# Battery_board_V4_3.net
KiCad netlist of a schematic drawn in EAGLE
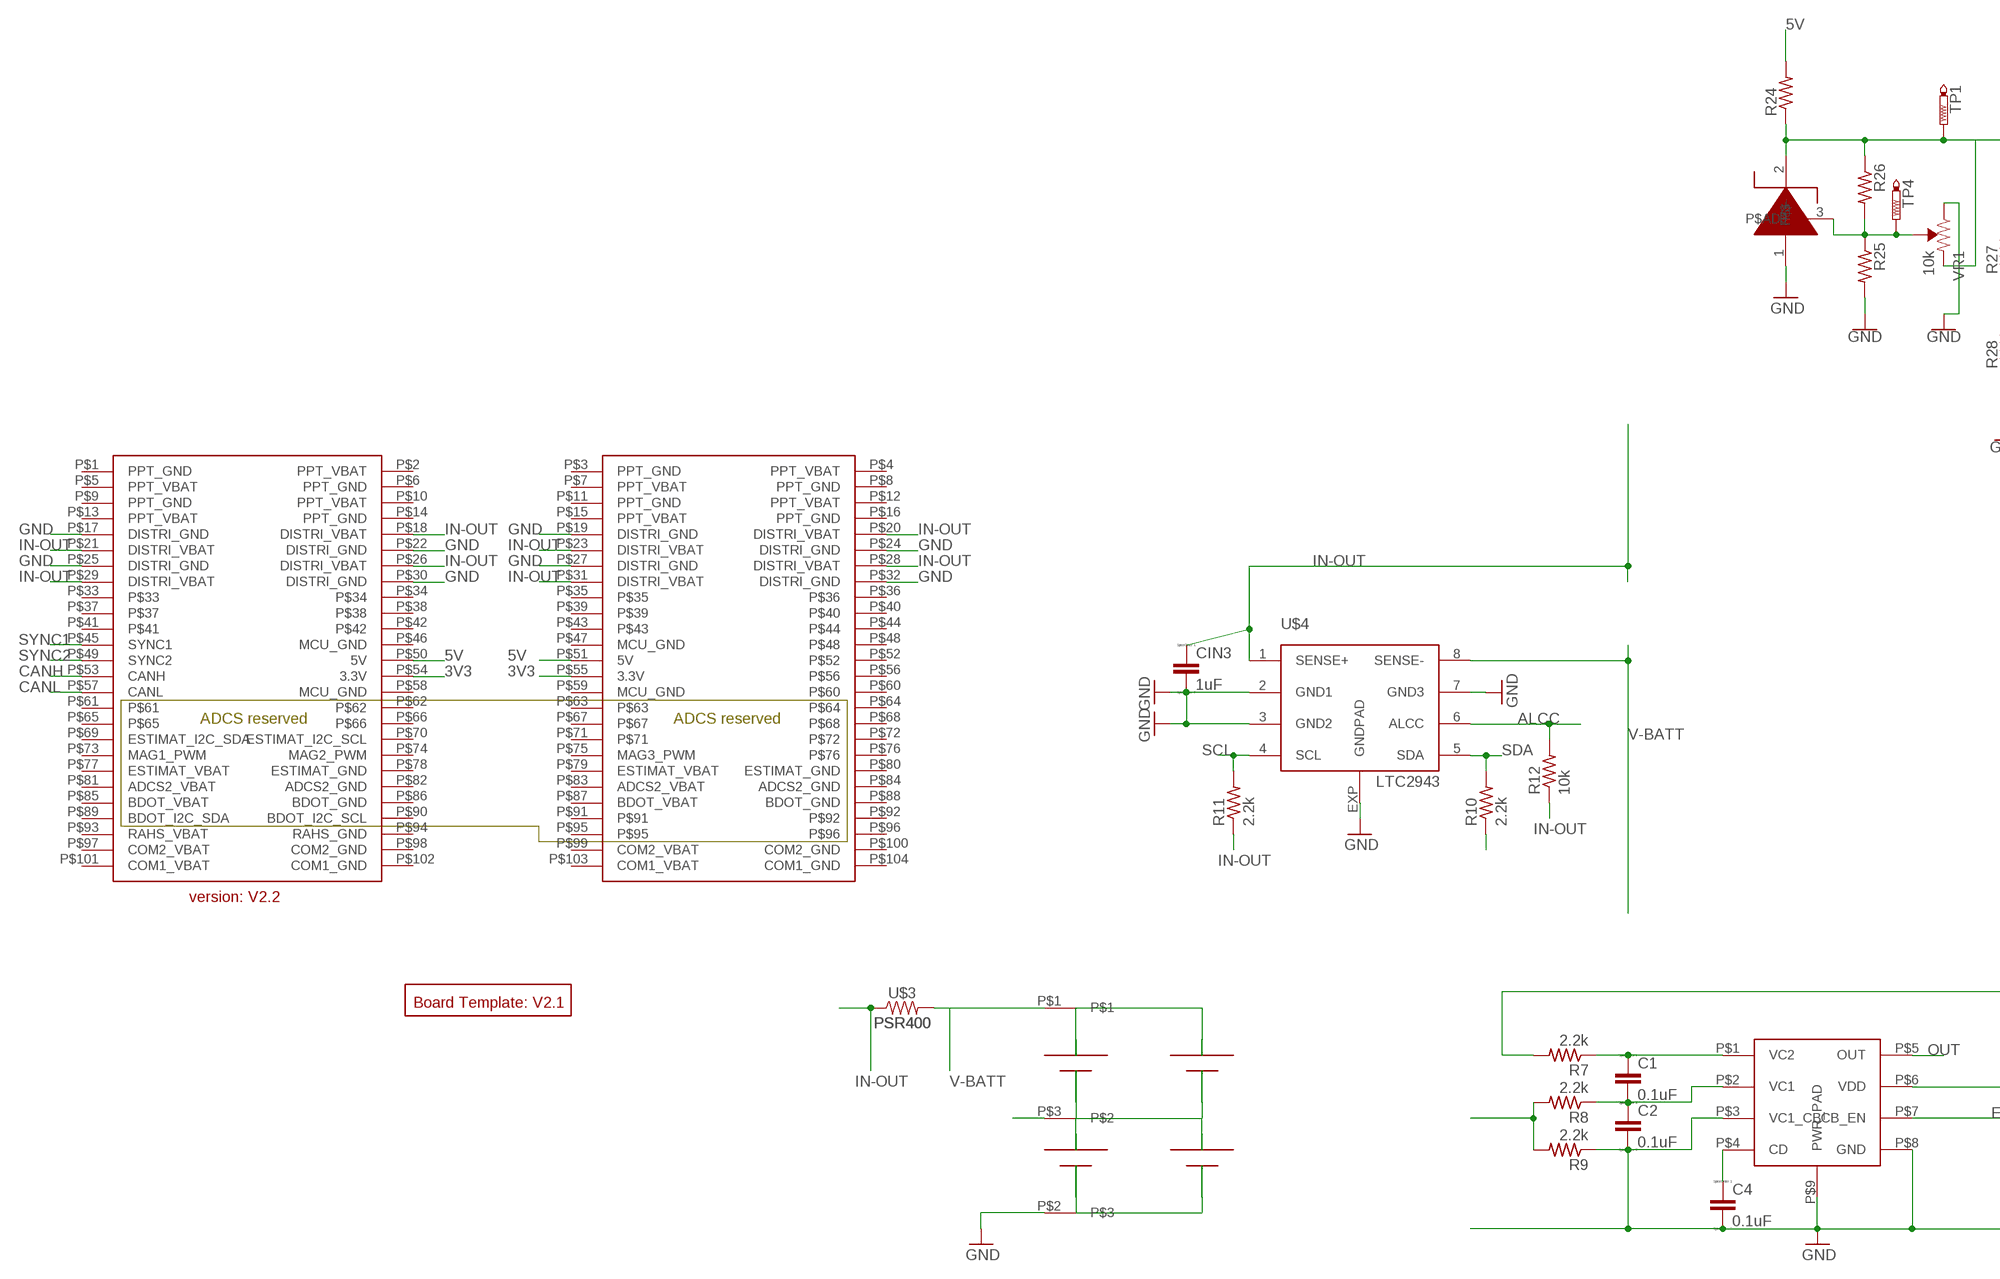
[diagram p0: schematic, sheet 1, part 1 of 2]
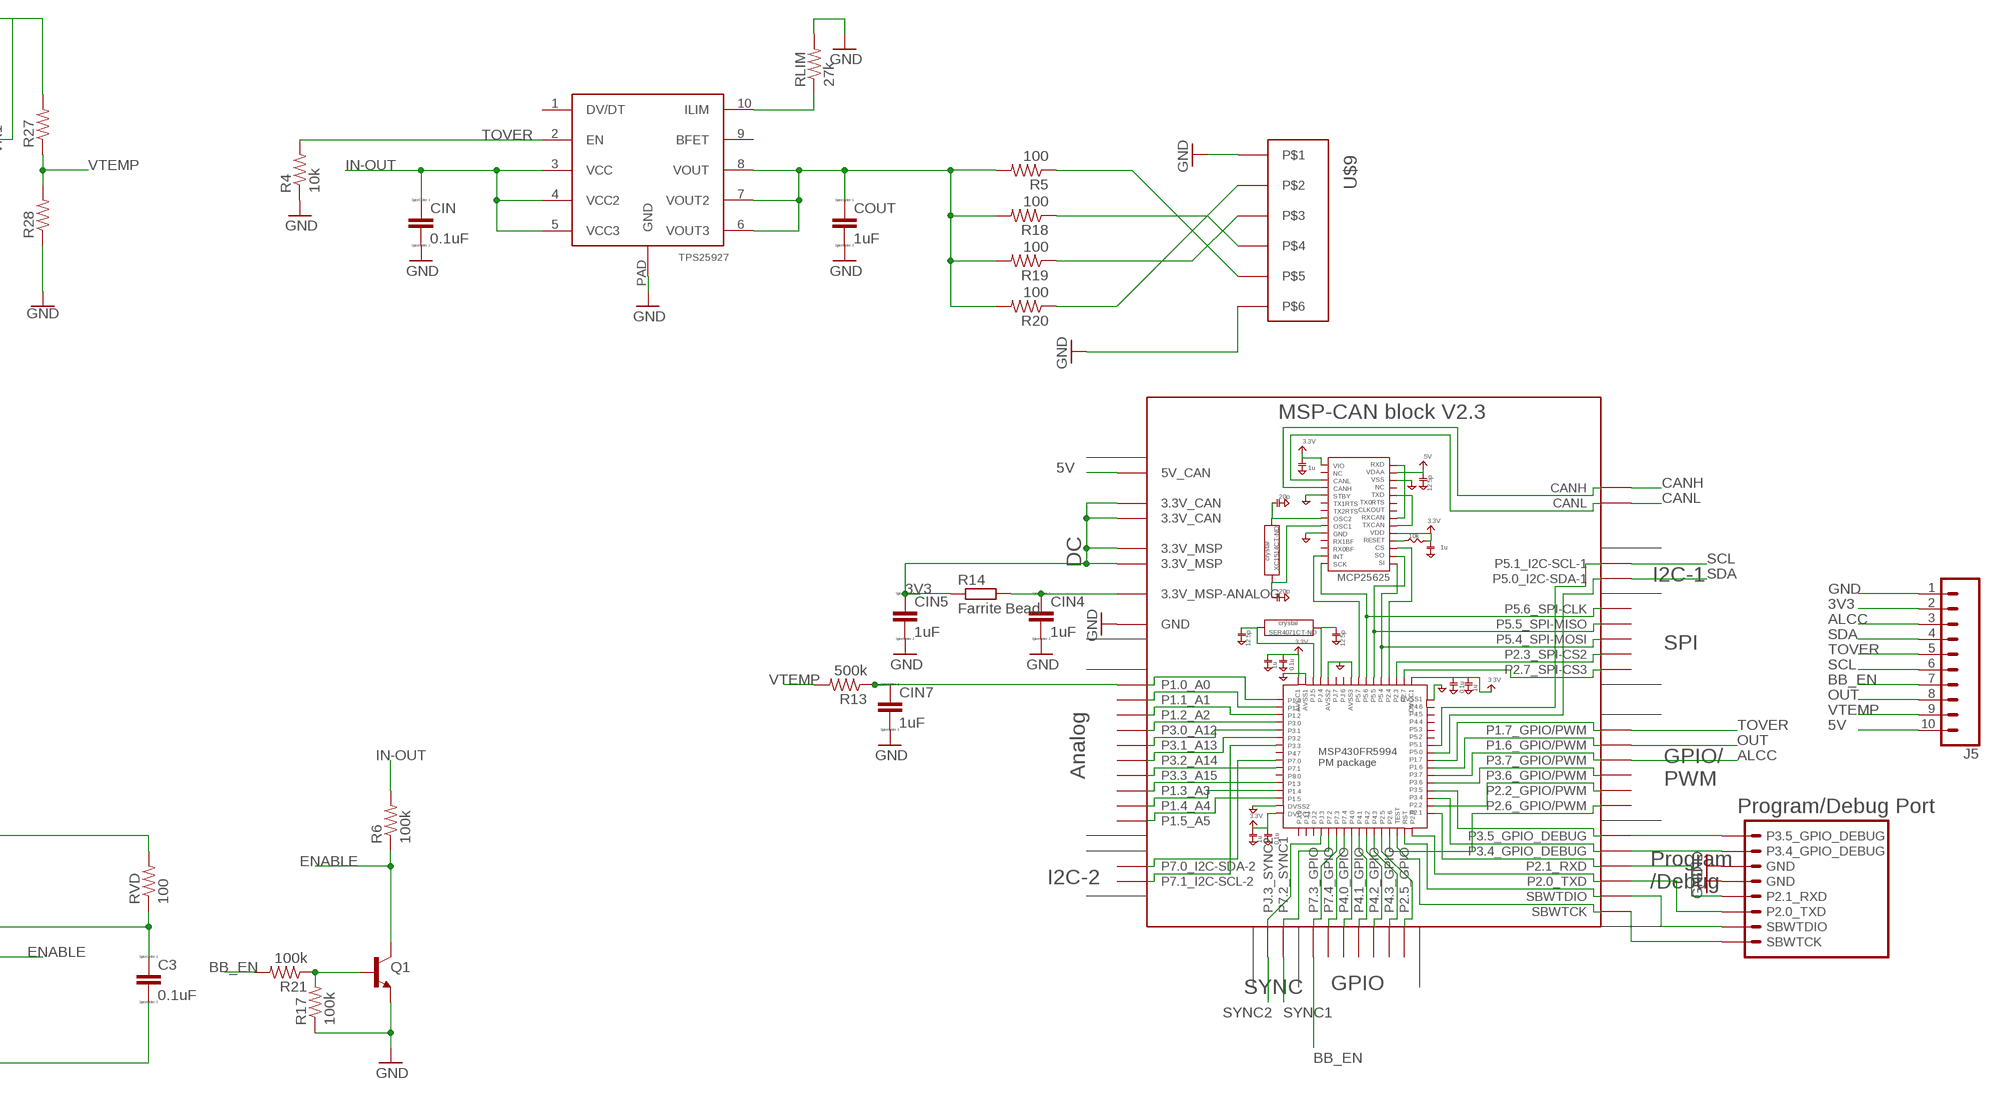
[diagram p1: schematic, sheet 1, part 2 of 2]

(export (version "E")
  (design (tool "Eeschema 10.0.6"))
  (components
    (comp (ref "C1")
      (value "0.1uF")
      (footprint "eagle-import:C0805")
      (libsource (lib "eagle-import") (part "C"))
    )
    (comp (ref "C2")
      (value "0.1uF")
      (footprint "eagle-import:C0805")
      (libsource (lib "eagle-import") (part "C"))
    )
    (comp (ref "C3")
      (value "0.1uF")
      (footprint "eagle-import:C0805")
      (libsource (lib "eagle-import") (part "C"))
    )
    (comp (ref "C4")
      (value "0.1uF")
      (footprint "eagle-import:C0805")
      (libsource (lib "eagle-import") (part "C"))
    )
    (comp (ref "CIN")
      (value "0.1uF")
      (footprint "eagle-import:C0805")
      (libsource (lib "eagle-import") (part "C"))
    )
    (comp (ref "CIN3")
      (value "1uF")
      (footprint "eagle-import:C0805")
      (libsource (lib "eagle-import") (part "C"))
    )
    (comp (ref "CIN4")
      (value "1uF")
      (footprint "eagle-import:C0805")
      (libsource (lib "eagle-import") (part "C"))
    )
    (comp (ref "CIN5")
      (value "1uF")
      (footprint "eagle-import:C0805")
      (libsource (lib "eagle-import") (part "C"))
    )
    (comp (ref "CIN7")
      (value "1uF")
      (footprint "eagle-import:C0805")
      (libsource (lib "eagle-import") (part "C"))
    )
    (comp (ref "COUT")
      (value "1uF")
      (footprint "eagle-import:C0805")
      (libsource (lib "eagle-import") (part "C"))
    )
    (comp (ref "J5")
      (value "CONN_10LOCK")
      (footprint "eagle-import:1X10_LOCK")
      (libsource (lib "eagle-import") (part "CONN_10LOCK"))
    )
    (comp (ref "Q1")
      (value "TRANS_NPN-MMBT2222AL")
      (footprint "eagle-import:SOT23-3")
      (libsource (lib "eagle-import") (part "TRANS_NPN-MMBT2222AL"))
    )
    (comp (ref "R4")
      (value "10k")
      (footprint "eagle-import:R0805")
      (libsource (lib "eagle-import") (part "R-US_R0805"))
    )
    (comp (ref "R5")
      (value "100")
      (footprint "eagle-import:R0805")
      (libsource (lib "eagle-import") (part "R-US_R0805"))
    )
    (comp (ref "R6")
      (value "100k")
      (footprint "eagle-import:R0805")
      (libsource (lib "eagle-import") (part "R-US_R0805"))
    )
    (comp (ref "R7")
      (value "2.2k")
      (footprint "eagle-import:R0805")
      (libsource (lib "eagle-import") (part "R-US_R0805"))
    )
    (comp (ref "R8")
      (value "2.2k")
      (footprint "eagle-import:R0805")
      (libsource (lib "eagle-import") (part "R-US_R0805"))
    )
    (comp (ref "R9")
      (value "2.2k")
      (footprint "eagle-import:R0805")
      (libsource (lib "eagle-import") (part "R-US_R0805"))
    )
    (comp (ref "R10")
      (value "2.2k")
      (footprint "eagle-import:R0805")
      (libsource (lib "eagle-import") (part "R-US_R0805"))
    )
    (comp (ref "R11")
      (value "2.2k")
      (footprint "eagle-import:R0805")
      (libsource (lib "eagle-import") (part "R-US_R0805"))
    )
    (comp (ref "R12")
      (value "10k")
      (footprint "eagle-import:R0805")
      (libsource (lib "eagle-import") (part "R-US_R0805"))
    )
    (comp (ref "R13")
      (value "500k")
      (footprint "eagle-import:R0805")
      (libsource (lib "eagle-import") (part "R-US_R0805"))
    )
    (comp (ref "R14")
      (value "Farrite Bead")
      (footprint "eagle-import:R1206")
      (libsource (lib "eagle-import") (part "R-EU_R1206"))
    )
    (comp (ref "R17")
      (value "100k")
      (footprint "eagle-import:M0805")
      (libsource (lib "eagle-import") (part "R-US_M0805"))
    )
    (comp (ref "R18")
      (value "100")
      (footprint "eagle-import:R0805")
      (libsource (lib "eagle-import") (part "R-US_R0805"))
    )
    (comp (ref "R19")
      (value "100")
      (footprint "eagle-import:R0805")
      (libsource (lib "eagle-import") (part "R-US_R0805"))
    )
    (comp (ref "R20")
      (value "100")
      (footprint "eagle-import:R0805")
      (libsource (lib "eagle-import") (part "R-US_R0805"))
    )
    (comp (ref "R21")
      (value "100k")
      (footprint "eagle-import:M0805")
      (libsource (lib "eagle-import") (part "R-US_M0805"))
    )
    (comp (ref "R24")
      (value "R-US_R0805")
      (footprint "eagle-import:R0805")
      (libsource (lib "eagle-import") (part "R-US_R0805"))
    )
    (comp (ref "R25")
      (value "R-US_R0805")
      (footprint "eagle-import:R0805")
      (libsource (lib "eagle-import") (part "R-US_R0805"))
    )
    (comp (ref "R26")
      (value "R-US_R0805")
      (footprint "eagle-import:R0805")
      (libsource (lib "eagle-import") (part "R-US_R0805"))
    )
    (comp (ref "R27")
      (value "R-US_R0805")
      (footprint "eagle-import:R0805")
      (libsource (lib "eagle-import") (part "R-US_R0805"))
    )
    (comp (ref "R28")
      (value "R-US_R0805")
      (footprint "eagle-import:R0805")
      (libsource (lib "eagle-import") (part "R-US_R0805"))
    )
    (comp (ref "RLIM")
      (value "27k")
      (footprint "eagle-import:R0805")
      (libsource (lib "eagle-import") (part "R-US_R0805"))
    )
    (comp (ref "RVD")
      (value "100")
      (footprint "eagle-import:R0805")
      (libsource (lib "eagle-import") (part "R-US_R0805"))
    )
    (comp (ref "TP1")
      (value "PTR1PAD1-13Y")
      (footprint "eagle-import:P1-13Y")
      (libsource (lib "eagle-import") (part "PTR1PAD1-13Y"))
    )
    (comp (ref "TP4")
      (value "PTR1PAD1-13Y")
      (footprint "eagle-import:P1-13Y")
      (libsource (lib "eagle-import") (part "PTR1PAD1-13Y"))
    )
    (comp (ref "U$1")
      (value "MSP-CAN_BLOCK")
      (footprint "eagle-import:MSP-CAN_BLOCK")
      (libsource (lib "eagle-import") (part "MSP-CAN_BLOCK"))
    )
    (comp (ref "U$2")
      (value "PROGRAM/DEBUG_PORT")
      (footprint "eagle-import:1X08_CONNECTOR")
      (libsource (lib "eagle-import") (part "PROGRAM/DEBUG_PORT"))
    )
    (comp (ref "U$3")
      (value "PSR400")
      (footprint "eagle-import:PSR400")
      (libsource (lib "eagle-import") (part "PSR400"))
    )
    (comp (ref "U$4")
      (value "LTC2943")
      (footprint "eagle-import:DFN8(3X3)LT")
      (libsource (lib "eagle-import") (part "LTC2943"))
    )
    (comp (ref "U$5")
      (value "TPS252927")
      (footprint "eagle-import:VSON10")
      (libsource (lib "eagle-import") (part "TPS252927"))
    )
    (comp (ref "U$6")
      (value "POWER_PACK")
      (footprint "eagle-import:BATTERY_PACK")
      (libsource (lib "eagle-import") (part "POWER_PACK"))
    )
    (comp (ref "U$7")
      (value "PC104_CONNECTOR")
      (footprint "eagle-import:PC104_CONNECTOR")
      (libsource (lib "eagle-import") (part "PC104_CONNECTOR"))
    )
    (comp (ref "U$8")
      (value "BQ29209")
      (footprint "eagle-import:VSON8")
      (libsource (lib "eagle-import") (part "BQ29209"))
    )
    (comp (ref "U$9")
      (value "PICOLOCK_6")
      (footprint "eagle-import:PICOLOCK_6")
      (libsource (lib "eagle-import") (part "PICOLOCK_6"))
    )
    (comp (ref "U$10")
      (value "LM135Z")
      (footprint "eagle-import:TO-92-3")
      (libsource (lib "eagle-import") (part "LM135Z"))
    )
    (comp (ref "U$11")
      (value "BOARD_TEMPLATE")
      (footprint "eagle-import:BOARD_TEMPLATE")
      (libsource (lib "eagle-import") (part "BOARD_TEMPLATE"))
    )
    (comp (ref "VR1")
      (value "10k")
      (footprint "eagle-import:TRIMPOT-SMD-TC33X")
      (libsource (lib "eagle-import") (part "TRIMPOT-SMD-3MM-OPEN-1/10W-25%"))
    )
  )
  (nets
    (net (code "1") (name "/3V3") (class "Default")
      (node (ref "CIN5") (pin "1") (pinfunction "1_1") (pintype "passive"))
      (node (ref "J5") (pin "2") (pinfunction "2_2") (pintype "passive"))
      (node (ref "R14") (pin "1") (pinfunction "1_1") (pintype "passive"))
      (node (ref "U$1") (pin "3.3V@CAN1") (pinfunction "3.3V_CAN_3.3V@CAN1") (pintype "bidirectional"))
      (node (ref "U$1") (pin "3.3V@CAN2") (pinfunction "3.3V_CAN_3.3V@CAN2") (pintype "bidirectional"))
      (node (ref "U$1") (pin "3.3V@MSP1") (pinfunction "3.3V_MSP_3.3V@MSP1") (pintype "bidirectional"))
      (node (ref "U$1") (pin "3.3V@MSP2") (pinfunction "3.3V_MSP_3.3V@MSP2") (pintype "bidirectional"))
      (node (ref "U$7") (pin "P$54") (pinfunction "3.3V_P$54") (pintype "bidirectional"))
      (node (ref "U$7") (pin "P$55") (pinfunction "3.3V_P$55") (pintype "bidirectional"))
    )
    (net (code "2") (name "/5V") (class "Default")
      (node (ref "J5") (pin "10") (pinfunction "10_10") (pintype "passive"))
      (node (ref "R24") (pin "2") (pinfunction "2_2") (pintype "passive"))
      (node (ref "U$1") (pin "5V") (pinfunction "5V_CAN_5V") (pintype "bidirectional"))
      (node (ref "U$7") (pin "P$50") (pinfunction "5V_P$50") (pintype "bidirectional"))
      (node (ref "U$7") (pin "P$51") (pinfunction "5V_P$51") (pintype "bidirectional"))
    )
    (net (code "3") (name "/ALCC") (class "Default")
      (node (ref "J5") (pin "3") (pinfunction "3_3") (pintype "passive"))
      (node (ref "R12") (pin "2") (pinfunction "2_2") (pintype "passive"))
      (node (ref "U$1") (pin "P3.7_GPIO/PWM") (pinfunction "P3.7_GPIO/PWM_P3.7_GPIO/PWM") (pintype "bidirectional"))
      (node (ref "U$4") (pin "6") (pinfunction "ALCC_6") (pintype "bidirectional"))
    )
    (net (code "4") (name "/BB_EN") (class "Default")
      (node (ref "J5") (pin "7") (pinfunction "7_7") (pintype "passive"))
      (node (ref "R21") (pin "2") (pinfunction "2_2") (pintype "passive"))
      (node (ref "U$1") (pin "P7.3_GPIO") (pinfunction "P7.3_GPIO_P7.3_GPIO") (pintype "bidirectional"))
    )
    (net (code "5") (name "/BT-NODE") (class "Default")
      (node (ref "R8") (pin "2") (pinfunction "2_2") (pintype "passive"))
      (node (ref "R9") (pin "2") (pinfunction "2_2") (pintype "passive"))
      (node (ref "U$6") (pin "P$3") (pinfunction "P$2_P$3") (pintype "bidirectional"))
    )
    (net (code "6") (name "/CANH") (class "Default")
      (node (ref "U$1") (pin "CANH") (pinfunction "CANH_CANH") (pintype "bidirectional"))
      (node (ref "U$7") (pin "P$53") (pinfunction "CANH_P$53") (pintype "bidirectional"))
    )
    (net (code "7") (name "/CANL") (class "Default")
      (node (ref "U$1") (pin "CANL") (pinfunction "CANL_CANL") (pintype "bidirectional"))
      (node (ref "U$7") (pin "P$57") (pinfunction "CANL_P$57") (pintype "bidirectional"))
    )
    (net (code "8") (name "/ENABLE") (class "Default")
      (node (ref "Q1") (pin "3") (pinfunction "C_3") (pintype "passive"))
      (node (ref "R6") (pin "1") (pinfunction "1_1") (pintype "passive"))
      (node (ref "U$8") (pin "P$7") (pinfunction "CB_EN_P$7") (pintype "bidirectional"))
    )
    (net (code "9") (name "/IN-OUT") (class "Default")
      (node (ref "CIN") (pin "1") (pinfunction "1_1") (pintype "passive"))
      (node (ref "CIN3") (pin "1") (pinfunction "1_1") (pintype "passive"))
      (node (ref "R10") (pin "1") (pinfunction "1_1") (pintype "passive"))
      (node (ref "R11") (pin "1") (pinfunction "1_1") (pintype "passive"))
      (node (ref "R12") (pin "1") (pinfunction "1_1") (pintype "passive"))
      (node (ref "R6") (pin "2") (pinfunction "2_2") (pintype "passive"))
      (node (ref "R7") (pin "2") (pinfunction "2_2") (pintype "passive"))
      (node (ref "RVD") (pin "2") (pinfunction "2_2") (pintype "passive"))
      (node (ref "U$3") (pin "P$1") (pinfunction "1_P$1") (pintype "passive"))
      (node (ref "U$4") (pin "1") (pinfunction "SENSE+_1") (pintype "bidirectional"))
      (node (ref "U$5") (pin "3") (pinfunction "VCC_3") (pintype "bidirectional"))
      (node (ref "U$5") (pin "4") (pinfunction "VCC2_4") (pintype "bidirectional"))
      (node (ref "U$5") (pin "5") (pinfunction "VCC3_5") (pintype "bidirectional"))
      (node (ref "U$7") (pin "P$18") (pinfunction "DISTRI_VBAT_P$18") (pintype "bidirectional"))
      (node (ref "U$7") (pin "P$20") (pinfunction "DISTRI_VBAT_P$20") (pintype "bidirectional"))
      (node (ref "U$7") (pin "P$21") (pinfunction "DISTRI_VBAT_P$21") (pintype "bidirectional"))
      (node (ref "U$7") (pin "P$23") (pinfunction "DISTRI_VBAT_P$23") (pintype "bidirectional"))
      (node (ref "U$7") (pin "P$26") (pinfunction "DISTRI_VBAT_P$26") (pintype "bidirectional"))
      (node (ref "U$7") (pin "P$28") (pinfunction "DISTRI_VBAT_P$28") (pintype "bidirectional"))
      (node (ref "U$7") (pin "P$29") (pinfunction "DISTRI_VBAT_P$29") (pintype "bidirectional"))
      (node (ref "U$7") (pin "P$31") (pinfunction "DISTRI_VBAT_P$31") (pintype "bidirectional"))
    )
    (net (code "10") (name "/OUT") (class "Default")
      (node (ref "J5") (pin "8") (pinfunction "8_8") (pintype "passive"))
      (node (ref "U$1") (pin "P1.6_GPIO/PWM") (pinfunction "P1.6_GPIO/PWM_P1.6_GPIO/PWM") (pintype "bidirectional"))
      (node (ref "U$8") (pin "P$5") (pinfunction "OUT_P$5") (pintype "bidirectional"))
    )
    (net (code "11") (name "/SCL") (class "Default")
      (node (ref "J5") (pin "6") (pinfunction "6_6") (pintype "passive"))
      (node (ref "R11") (pin "2") (pinfunction "2_2") (pintype "passive"))
      (node (ref "U$1") (pin "P5.1_I2C-SCL-1") (pinfunction "P5.1_I2C-SCL-1_P5.1_I2C-SCL-1") (pintype "bidirectional"))
      (node (ref "U$4") (pin "4") (pinfunction "SCL_4") (pintype "bidirectional"))
    )
    (net (code "12") (name "/SDA") (class "Default")
      (node (ref "J5") (pin "4") (pinfunction "4_4") (pintype "passive"))
      (node (ref "R10") (pin "2") (pinfunction "2_2") (pintype "passive"))
      (node (ref "U$1") (pin "P5.0_I2C-SDA-1") (pinfunction "P5.0_I2C-SDA-1_P5.0_I2C-SDA-1") (pintype "bidirectional"))
      (node (ref "U$4") (pin "5") (pinfunction "SDA_5") (pintype "bidirectional"))
    )
    (net (code "13") (name "/SYNC1") (class "Default")
      (node (ref "U$1") (pin "P7.2_SYNC1") (pinfunction "P7.2_SYNC1_P7.2_SYNC1") (pintype "bidirectional"))
      (node (ref "U$7") (pin "P$45") (pinfunction "SYNC1_P$45") (pintype "bidirectional"))
    )
    (net (code "14") (name "/SYNC2") (class "Default")
      (node (ref "U$1") (pin "PJ.3_SYNC2") (pinfunction "PJ.3_SYNC2_PJ.3_SYNC2") (pintype "bidirectional"))
      (node (ref "U$7") (pin "P$49") (pinfunction "SYNC2_P$49") (pintype "bidirectional"))
    )
    (net (code "15") (name "/TOVER") (class "Default")
      (node (ref "J5") (pin "5") (pinfunction "5_5") (pintype "passive"))
      (node (ref "R4") (pin "2") (pinfunction "2_2") (pintype "passive"))
      (node (ref "U$1") (pin "P1.7_GPIO/PWM") (pinfunction "P1.7_GPIO/PWM_P1.7_GPIO/PWM") (pintype "bidirectional"))
      (node (ref "U$5") (pin "2") (pinfunction "EN_2") (pintype "bidirectional"))
    )
    (net (code "16") (name "/V-BATT") (class "Default")
      (node (ref "U$3") (pin "P$2") (pinfunction "2_P$2") (pintype "passive"))
      (node (ref "U$4") (pin "8") (pinfunction "SENSE-_8") (pintype "bidirectional"))
      (node (ref "U$6") (pin "P$1") (pinfunction "P$1_P$1") (pintype "bidirectional"))
    )
    (net (code "17") (name "/VTEMP") (class "Default")
      (node (ref "J5") (pin "9") (pinfunction "9_9") (pintype "passive"))
      (node (ref "R13") (pin "2") (pinfunction "2_2") (pintype "passive"))
      (node (ref "R27") (pin "1") (pinfunction "1_1") (pintype "passive"))
      (node (ref "R28") (pin "2") (pinfunction "2_2") (pintype "passive"))
    )
    (net (code "18") (name "GND") (class "Default")
      (node (ref "C2") (pin "2") (pinfunction "2_2") (pintype "passive"))
      (node (ref "C3") (pin "2") (pinfunction "2_2") (pintype "passive"))
      (node (ref "C4") (pin "2") (pinfunction "2_2") (pintype "passive"))
      (node (ref "CIN") (pin "2") (pinfunction "2_2") (pintype "passive"))
      (node (ref "CIN3") (pin "2") (pinfunction "2_2") (pintype "passive"))
      (node (ref "CIN4") (pin "2") (pinfunction "2_2") (pintype "passive"))
      (node (ref "CIN5") (pin "2") (pinfunction "2_2") (pintype "passive"))
      (node (ref "CIN7") (pin "2") (pinfunction "2_2") (pintype "passive"))
      (node (ref "COUT") (pin "2") (pinfunction "2_2") (pintype "passive"))
      (node (ref "J5") (pin "1") (pinfunction "1_1") (pintype "passive"))
      (node (ref "Q1") (pin "2") (pinfunction "E_2") (pintype "passive"))
      (node (ref "R17") (pin "1") (pinfunction "1_1") (pintype "passive"))
      (node (ref "R25") (pin "2") (pinfunction "2_2") (pintype "passive"))
      (node (ref "R28") (pin "1") (pinfunction "1_1") (pintype "passive"))
      (node (ref "R4") (pin "1") (pinfunction "1_1") (pintype "passive"))
      (node (ref "R9") (pin "1") (pinfunction "1_1") (pintype "passive"))
      (node (ref "RLIM") (pin "2") (pinfunction "2_2") (pintype "passive"))
      (node (ref "U$1") (pin "GND@1") (pinfunction "GND_GND@1") (pintype "bidirectional"))
      (node (ref "U$1") (pin "GND@10") (pinfunction "GND_GND@10") (pintype "bidirectional"))
      (node (ref "U$1") (pin "GND@11") (pinfunction "GND_GND@11") (pintype "bidirectional"))
      (node (ref "U$1") (pin "GND@12") (pinfunction "GND_GND@12") (pintype "bidirectional"))
      (node (ref "U$1") (pin "GND@13") (pinfunction "GND_GND@13") (pintype "bidirectional"))
      (node (ref "U$1") (pin "GND@14") (pinfunction "GND_GND@14") (pintype "bidirectional"))
      (node (ref "U$1") (pin "GND@15") (pinfunction "GND_GND@15") (pintype "bidirectional"))
      (node (ref "U$1") (pin "GND@16") (pinfunction "GND_GND@16") (pintype "bidirectional"))
      (node (ref "U$1") (pin "GND@17") (pinfunction "GND_GND@17") (pintype "bidirectional"))
      (node (ref "U$1") (pin "GND@2") (pinfunction "GND_GND@2") (pintype "bidirectional"))
      (node (ref "U$1") (pin "GND@26") (pinfunction "GND_GND@26") (pintype "bidirectional"))
      (node (ref "U$1") (pin "GND@3") (pinfunction "GND_GND@3") (pintype "bidirectional"))
      (node (ref "U$1") (pin "GND@4") (pinfunction "GND_GND@4") (pintype "bidirectional"))
      (node (ref "U$1") (pin "GND@5") (pinfunction "GND_GND@5") (pintype "bidirectional"))
      (node (ref "U$1") (pin "GND@7") (pinfunction "GND_GND@7") (pintype "bidirectional"))
      (node (ref "U$1") (pin "GND@8") (pinfunction "GND_GND@8") (pintype "bidirectional"))
      (node (ref "U$1") (pin "GND@9") (pinfunction "GND_GND@9") (pintype "bidirectional"))
      (node (ref "U$10") (pin "1") (pinfunction "P$-_1") (pintype "bidirectional"))
      (node (ref "U$2") (pin "5") (pinfunction "GND_5") (pintype "bidirectional"))
      (node (ref "U$2") (pin "6") (pinfunction "GND_6") (pintype "bidirectional"))
      (node (ref "U$4") (pin "2") (pinfunction "GND1_2") (pintype "bidirectional"))
      (node (ref "U$4") (pin "3") (pinfunction "GND2_3") (pintype "bidirectional"))
      (node (ref "U$4") (pin "7") (pinfunction "GND3_7") (pintype "bidirectional"))
      (node (ref "U$4") (pin "EXP") (pinfunction "GNDPAD_EXP") (pintype "bidirectional"))
      (node (ref "U$5") (pin "PAD") (pinfunction "GND_PAD") (pintype "bidirectional"))
      (node (ref "U$6") (pin "P$2") (pinfunction "P$3_P$2") (pintype "bidirectional"))
      (node (ref "U$7") (pin "P$17") (pinfunction "DISTRI_GND_P$17") (pintype "bidirectional"))
      (node (ref "U$7") (pin "P$19") (pinfunction "DISTRI_GND_P$19") (pintype "bidirectional"))
      (node (ref "U$7") (pin "P$22") (pinfunction "DISTRI_GND_P$22") (pintype "bidirectional"))
      (node (ref "U$7") (pin "P$24") (pinfunction "DISTRI_GND_P$24") (pintype "bidirectional"))
      (node (ref "U$7") (pin "P$25") (pinfunction "DISTRI_GND_P$25") (pintype "bidirectional"))
      (node (ref "U$7") (pin "P$27") (pinfunction "DISTRI_GND_P$27") (pintype "bidirectional"))
      (node (ref "U$7") (pin "P$30") (pinfunction "DISTRI_GND_P$30") (pintype "bidirectional"))
      (node (ref "U$7") (pin "P$32") (pinfunction "DISTRI_GND_P$32") (pintype "bidirectional"))
      (node (ref "U$8") (pin "P$3") (pinfunction "VC1_CB_P$3") (pintype "bidirectional"))
      (node (ref "U$8") (pin "P$8") (pinfunction "GND_P$8") (pintype "bidirectional"))
      (node (ref "U$8") (pin "P$9") (pinfunction "PWR_PAD_P$9") (pintype "bidirectional"))
      (node (ref "U$9") (pin "P$1") (pinfunction "P$1_P$1") (pintype "bidirectional"))
      (node (ref "U$9") (pin "P$6") (pinfunction "P$6_P$6") (pintype "bidirectional"))
      (node (ref "VR1") (pin "1") (pinfunction "CW_1") (pintype "passive"))
    )
    (net (code "19") (name "Net-(CIN7-Pad1)") (class "Default")
      (node (ref "CIN7") (pin "1") (pinfunction "1_1") (pintype "passive"))
      (node (ref "R13") (pin "1") (pinfunction "1_1") (pintype "passive"))
      (node (ref "U$1") (pin "P1.0_A0") (pinfunction "P1.0_A0_P1.0_A0") (pintype "bidirectional"))
    )
    (net (code "20") (name "Net-(Q1-B)") (class "Default")
      (node (ref "Q1") (pin "1") (pinfunction "B_1") (pintype "passive"))
      (node (ref "R17") (pin "2") (pinfunction "2_2") (pintype "passive"))
      (node (ref "R21") (pin "1") (pinfunction "1_1") (pintype "passive"))
    )
    (net (code "21") (name "Net-(R5-Pad1)") (class "Default")
      (node (ref "R5") (pin "1") (pinfunction "1_1") (pintype "passive"))
      (node (ref "U$9") (pin "P$5") (pinfunction "P$5_P$5") (pintype "bidirectional"))
    )
    (net (code "22") (name "Net-(R18-Pad1)") (class "Default")
      (node (ref "R18") (pin "1") (pinfunction "1_1") (pintype "passive"))
      (node (ref "U$9") (pin "P$4") (pinfunction "P$4_P$4") (pintype "bidirectional"))
    )
    (net (code "23") (name "Net-(R19-Pad1)") (class "Default")
      (node (ref "R19") (pin "1") (pinfunction "1_1") (pintype "passive"))
      (node (ref "U$9") (pin "P$3") (pinfunction "P$3_P$3") (pintype "bidirectional"))
    )
    (net (code "24") (name "Net-(R20-Pad1)") (class "Default")
      (node (ref "R20") (pin "1") (pinfunction "1_1") (pintype "passive"))
      (node (ref "U$9") (pin "P$2") (pinfunction "P$2_P$2") (pintype "bidirectional"))
    )
    (net (code "25") (name "Net-(U$1-3.3V_MSP-ANALOG)") (class "Default")
      (node (ref "CIN4") (pin "1") (pinfunction "1_1") (pintype "passive"))
      (node (ref "R14") (pin "2") (pinfunction "2_2") (pintype "passive"))
      (node (ref "U$1") (pin "3.3V_ANALOG@MSP2") (pinfunction "3.3V_MSP-ANALOG_3.3V_ANALOG@MSP2") (pintype "bidirectional"))
    )
    (net (code "26") (name "Net-(U$1-PadSBWTCK)") (class "Default")
      (node (ref "U$1") (pin "SBWTCK") (pinfunction "SBWTCK_SBWTCK") (pintype "bidirectional"))
      (node (ref "U$2") (pin "SBWTCK") (pinfunction "SBWTCK_SBWTCK") (pintype "bidirectional"))
    )
    (net (code "27") (name "Net-(U$2-P2.0_TXD)") (class "Default")
      (node (ref "U$1") (pin "P2.0_TXD") (pinfunction "P2.0_TXD_P2.0_TXD") (pintype "bidirectional"))
      (node (ref "U$2") (pin "3") (pinfunction "P2.0_TXD_3") (pintype "bidirectional"))
    )
    (net (code "28") (name "Net-(U$2-P2.1_RXD)") (class "Default")
      (node (ref "U$1") (pin "P2.1_RXD") (pinfunction "P2.1_RXD_P2.1_RXD") (pintype "bidirectional"))
      (node (ref "U$2") (pin "4") (pinfunction "P2.1_RXD_4") (pintype "bidirectional"))
    )
    (net (code "29") (name "Net-(U$2-P3.4_GPIO_DEBUG)") (class "Default")
      (node (ref "U$1") (pin "P3.4_GPIO_DEBUG") (pinfunction "P3.4_GPIO_DEBUG_P3.4_GPIO_DEBUG") (pintype "bidirectional"))
      (node (ref "U$2") (pin "7") (pinfunction "P3.4_GPIO_DEBUG_7") (pintype "bidirectional"))
    )
    (net (code "30") (name "Net-(U$2-P3.5_GPIO_DEBUG)") (class "Default")
      (node (ref "U$1") (pin "P3.5_GPIO_DEBUG") (pinfunction "P3.5_GPIO_DEBUG_P3.5_GPIO_DEBUG") (pintype "bidirectional"))
      (node (ref "U$2") (pin "8") (pinfunction "P3.5_GPIO_DEBUG_8") (pintype "bidirectional"))
    )
    (net (code "31") (name "Net-(U$2-SBWTDIO)") (class "Default")
      (node (ref "U$1") (pin "SBWTDIO") (pinfunction "SBWTDIO_SBWTDIO") (pintype "bidirectional"))
      (node (ref "U$2") (pin "2") (pinfunction "SBWTDIO_2") (pintype "bidirectional"))
    )
    (net (code "32") (name "Net-(U$5-ILIM)") (class "Default")
      (node (ref "RLIM") (pin "1") (pinfunction "1_1") (pintype "passive"))
      (node (ref "U$5") (pin "10") (pinfunction "ILIM_10") (pintype "bidirectional"))
    )
    (net (code "33") (name "Net-(U$5-VOUT)") (class "Default")
      (node (ref "COUT") (pin "1") (pinfunction "1_1") (pintype "passive"))
      (node (ref "R18") (pin "2") (pinfunction "2_2") (pintype "passive"))
      (node (ref "R19") (pin "2") (pinfunction "2_2") (pintype "passive"))
      (node (ref "R20") (pin "2") (pinfunction "2_2") (pintype "passive"))
      (node (ref "R5") (pin "2") (pinfunction "2_2") (pintype "passive"))
      (node (ref "U$5") (pin "6") (pinfunction "VOUT3_6") (pintype "bidirectional"))
      (node (ref "U$5") (pin "7") (pinfunction "VOUT2_7") (pintype "bidirectional"))
      (node (ref "U$5") (pin "8") (pinfunction "VOUT_8") (pintype "bidirectional"))
    )
    (net (code "34") (name "Net-(U$8-CD)") (class "Default")
      (node (ref "C4") (pin "1") (pinfunction "1_1") (pintype "passive"))
      (node (ref "U$8") (pin "P$4") (pinfunction "CD_P$4") (pintype "bidirectional"))
    )
    (net (code "35") (name "Net-(U$8-VC1)") (class "Default")
      (node (ref "C1") (pin "2") (pinfunction "2_2") (pintype "passive"))
      (node (ref "C2") (pin "1") (pinfunction "1_1") (pintype "passive"))
      (node (ref "R8") (pin "1") (pinfunction "1_1") (pintype "passive"))
      (node (ref "U$8") (pin "P$2") (pinfunction "VC1_P$2") (pintype "bidirectional"))
    )
    (net (code "36") (name "Net-(U$8-VC2)") (class "Default")
      (node (ref "C1") (pin "1") (pinfunction "1_1") (pintype "passive"))
      (node (ref "R7") (pin "1") (pinfunction "1_1") (pintype "passive"))
      (node (ref "U$8") (pin "P$1") (pinfunction "VC2_P$1") (pintype "bidirectional"))
    )
    (net (code "37") (name "Net-(U$8-VDD)") (class "Default")
      (node (ref "C3") (pin "1") (pinfunction "1_1") (pintype "passive"))
      (node (ref "RVD") (pin "1") (pinfunction "1_1") (pintype "passive"))
      (node (ref "U$8") (pin "P$6") (pinfunction "VDD_P$6") (pintype "bidirectional"))
    )
    (net (code "38") (name "Net-(U$10-P$+)") (class "Default")
      (node (ref "R24") (pin "1") (pinfunction "1_1") (pintype "passive"))
      (node (ref "R26") (pin "1") (pinfunction "1_1") (pintype "passive"))
      (node (ref "R27") (pin "2") (pinfunction "2_2") (pintype "passive"))
      (node (ref "TP1") (pin "TP") (pinfunction "TP_TP") (pintype "input"))
      (node (ref "U$10") (pin "2") (pinfunction "P$+_2") (pintype "bidirectional"))
      (node (ref "VR1") (pin "3") (pinfunction "CCW_3") (pintype "passive"))
    )
    (net (code "39") (name "Net-(U$10-P$ADJ)") (class "Default")
      (node (ref "R25") (pin "1") (pinfunction "1_1") (pintype "passive"))
      (node (ref "R26") (pin "2") (pinfunction "2_2") (pintype "passive"))
      (node (ref "TP4") (pin "TP") (pinfunction "TP_TP") (pintype "input"))
      (node (ref "U$10") (pin "3") (pinfunction "P$ADJ_3") (pintype "bidirectional"))
      (node (ref "VR1") (pin "2") (pinfunction "WIPER_2") (pintype "passive"))
    )
    (net (code "40") (name "unconnected-(U$1-P2.3_SPI-CS2-PadP2.4_SPI-CS2)") (class "Default")
      (node (ref "U$1") (pin "P2.4_SPI-CS2") (pinfunction "P2.3_SPI-CS2_P2.4_SPI-CS2") (pintype "bidirectional"))
    )
    (net (code "41") (name "unconnected-(U$1-PadP1.1_A1)") (class "Default")
      (node (ref "U$1") (pin "P1.1_A1") (pinfunction "P1.1_A1_P1.1_A1") (pintype "bidirectional"))
    )
    (net (code "42") (name "unconnected-(U$1-PadP1.2_A2)") (class "Default")
      (node (ref "U$1") (pin "P1.2_A2") (pinfunction "P1.2_A2_P1.2_A2") (pintype "bidirectional"))
    )
    (net (code "43") (name "unconnected-(U$1-PadP1.3_A3)") (class "Default")
      (node (ref "U$1") (pin "P1.3_A3") (pinfunction "P1.3_A3_P1.3_A3") (pintype "bidirectional"))
    )
    (net (code "44") (name "unconnected-(U$1-PadP1.4_A4)") (class "Default")
      (node (ref "U$1") (pin "P1.4_A4") (pinfunction "P1.4_A4_P1.4_A4") (pintype "bidirectional"))
    )
    (net (code "45") (name "unconnected-(U$1-PadP1.5_A5)") (class "Default")
      (node (ref "U$1") (pin "P1.5_A5") (pinfunction "P1.5_A5_P1.5_A5") (pintype "bidirectional"))
    )
    (net (code "46") (name "unconnected-(U$1-PadP2.2_GPIO{slash}PWM)") (class "Default")
      (node (ref "U$1") (pin "P2.2_GPIO/PWM") (pinfunction "P2.2_GPIO/PWM_P2.2_GPIO/PWM") (pintype "bidirectional"))
    )
    (net (code "47") (name "unconnected-(U$1-PadP2.5_GPIO)") (class "Default")
      (node (ref "U$1") (pin "P2.5_GPIO") (pinfunction "P2.5_GPIO_P2.5_GPIO") (pintype "bidirectional"))
    )
    (net (code "48") (name "unconnected-(U$1-PadP2.6_GPIO{slash}PWM)") (class "Default")
      (node (ref "U$1") (pin "P2.6_GPIO/PWM") (pinfunction "P2.6_GPIO/PWM_P2.6_GPIO/PWM") (pintype "bidirectional"))
    )
    (net (code "49") (name "unconnected-(U$1-PadP2.7_SPI-CS3)") (class "Default")
      (node (ref "U$1") (pin "P2.7_SPI-CS3") (pinfunction "P2.7_SPI-CS3_P2.7_SPI-CS3") (pintype "bidirectional"))
    )
    (net (code "50") (name "unconnected-(U$1-PadP3.0_A12)") (class "Default")
      (node (ref "U$1") (pin "P3.0_A12") (pinfunction "P3.0_A12_P3.0_A12") (pintype "bidirectional"))
    )
    (net (code "51") (name "unconnected-(U$1-PadP3.1_A13)") (class "Default")
      (node (ref "U$1") (pin "P3.1_A13") (pinfunction "P3.1_A13_P3.1_A13") (pintype "bidirectional"))
    )
    (net (code "52") (name "unconnected-(U$1-PadP3.2_A14)") (class "Default")
      (node (ref "U$1") (pin "P3.2_A14") (pinfunction "P3.2_A14_P3.2_A14") (pintype "bidirectional"))
    )
    (net (code "53") (name "unconnected-(U$1-PadP3.3_A15)") (class "Default")
      (node (ref "U$1") (pin "P3.3_A15") (pinfunction "P3.3_A15_P3.3_A15") (pintype "bidirectional"))
    )
    (net (code "54") (name "unconnected-(U$1-PadP3.6_GPIO{slash}PWM)") (class "Default")
      (node (ref "U$1") (pin "P3.6_GPIO/PWM") (pinfunction "P3.6_GPIO/PWM_P3.6_GPIO/PWM") (pintype "bidirectional"))
    )
    (net (code "55") (name "unconnected-(U$1-PadP4.0_GPIO)") (class "Default")
      (node (ref "U$1") (pin "P4.0_GPIO") (pinfunction "P4.0_GPIO_P4.0_GPIO") (pintype "bidirectional"))
    )
    (net (code "56") (name "unconnected-(U$1-PadP4.1_GPIO)") (class "Default")
      (node (ref "U$1") (pin "P4.1_GPIO") (pinfunction "P4.1_GPIO_P4.1_GPIO") (pintype "bidirectional"))
    )
    (net (code "57") (name "unconnected-(U$1-PadP4.2_GPIO)") (class "Default")
      (node (ref "U$1") (pin "P4.2_GPIO") (pinfunction "P4.2_GPIO_P4.2_GPIO") (pintype "bidirectional"))
    )
    (net (code "58") (name "unconnected-(U$1-PadP4.3_GPIO)") (class "Default")
      (node (ref "U$1") (pin "P4.3_GPIO") (pinfunction "P4.3_GPIO_P4.3_GPIO") (pintype "bidirectional"))
    )
    (net (code "59") (name "unconnected-(U$1-PadP5.4_SPI-MOSI)") (class "Default")
      (node (ref "U$1") (pin "P5.4_SPI-MOSI") (pinfunction "P5.4_SPI-MOSI_P5.4_SPI-MOSI") (pintype "bidirectional"))
    )
    (net (code "60") (name "unconnected-(U$1-PadP5.5_SPI-MISO)") (class "Default")
      (node (ref "U$1") (pin "P5.5_SPI-MISO") (pinfunction "P5.5_SPI-MISO_P5.5_SPI-MISO") (pintype "bidirectional"))
    )
    (net (code "61") (name "unconnected-(U$1-PadP5.6_SPI-CLK)") (class "Default")
      (node (ref "U$1") (pin "P5.6_SPI-CLK") (pinfunction "P5.6_SPI-CLK_P5.6_SPI-CLK") (pintype "bidirectional"))
    )
    (net (code "62") (name "unconnected-(U$1-PadP7.0_I2C-SDA-2)") (class "Default")
      (node (ref "U$1") (pin "P7.0_I2C-SDA-2") (pinfunction "P7.0_I2C-SDA-2_P7.0_I2C-SDA-2") (pintype "bidirectional"))
    )
    (net (code "63") (name "unconnected-(U$1-PadP7.1_I2C-SCL-2)") (class "Default")
      (node (ref "U$1") (pin "P7.1_I2C-SCL-2") (pinfunction "P7.1_I2C-SCL-2_P7.1_I2C-SCL-2") (pintype "bidirectional"))
    )
    (net (code "64") (name "unconnected-(U$1-PadP7.4_GPIO)") (class "Default")
      (node (ref "U$1") (pin "P7.4_GPIO") (pinfunction "P7.4_GPIO_P7.4_GPIO") (pintype "bidirectional"))
    )
    (net (code "65") (name "unconnected-(U$5-BFET-Pad9)") (class "Default")
      (node (ref "U$5") (pin "9") (pinfunction "BFET_9") (pintype "bidirectional"))
    )
    (net (code "66") (name "unconnected-(U$5-DV{slash}DT-Pad1)") (class "Default")
      (node (ref "U$5") (pin "1") (pinfunction "DV/DT_1") (pintype "bidirectional"))
    )
    (net (code "67") (name "unconnected-(U$7-ADCS2_GND-PadP$82)") (class "Default")
      (node (ref "U$7") (pin "P$82") (pinfunction "ADCS2_GND_P$82") (pintype "bidirectional"))
    )
    (net (code "68") (name "unconnected-(U$7-ADCS2_GND-PadP$84)") (class "Default")
      (node (ref "U$7") (pin "P$84") (pinfunction "ADCS2_GND_P$84") (pintype "bidirectional"))
    )
    (net (code "69") (name "unconnected-(U$7-ADCS2_VBAT-PadP$81)") (class "Default")
      (node (ref "U$7") (pin "P$81") (pinfunction "ADCS2_VBAT_P$81") (pintype "bidirectional"))
    )
    (net (code "70") (name "unconnected-(U$7-ADCS2_VBAT-PadP$83)") (class "Default")
      (node (ref "U$7") (pin "P$83") (pinfunction "ADCS2_VBAT_P$83") (pintype "bidirectional"))
    )
    (net (code "71") (name "unconnected-(U$7-BDOT_GND-PadP$86)") (class "Default")
      (node (ref "U$7") (pin "P$86") (pinfunction "BDOT_GND_P$86") (pintype "bidirectional"))
    )
    (net (code "72") (name "unconnected-(U$7-BDOT_GND-PadP$88)") (class "Default")
      (node (ref "U$7") (pin "P$88") (pinfunction "BDOT_GND_P$88") (pintype "bidirectional"))
    )
    (net (code "73") (name "unconnected-(U$7-BDOT_I2C_SCL-PadP$90)") (class "Default")
      (node (ref "U$7") (pin "P$90") (pinfunction "BDOT_I2C_SCL_P$90") (pintype "bidirectional"))
    )
    (net (code "74") (name "unconnected-(U$7-BDOT_I2C_SDA-PadP$89)") (class "Default")
      (node (ref "U$7") (pin "P$89") (pinfunction "BDOT_I2C_SDA_P$89") (pintype "bidirectional"))
    )
    (net (code "75") (name "unconnected-(U$7-BDOT_VBAT-PadP$85)") (class "Default")
      (node (ref "U$7") (pin "P$85") (pinfunction "BDOT_VBAT_P$85") (pintype "bidirectional"))
    )
    (net (code "76") (name "unconnected-(U$7-BDOT_VBAT-PadP$87)") (class "Default")
      (node (ref "U$7") (pin "P$87") (pinfunction "BDOT_VBAT_P$87") (pintype "bidirectional"))
    )
    (net (code "77") (name "unconnected-(U$7-COM1_GND-PadP$102)") (class "Default")
      (node (ref "U$7") (pin "P$102") (pinfunction "COM1_GND_P$102") (pintype "bidirectional"))
    )
    (net (code "78") (name "unconnected-(U$7-COM1_GND-PadP$104)") (class "Default")
      (node (ref "U$7") (pin "P$104") (pinfunction "COM1_GND_P$104") (pintype "bidirectional"))
    )
    (net (code "79") (name "unconnected-(U$7-COM1_VBAT-PadP$101)") (class "Default")
      (node (ref "U$7") (pin "P$101") (pinfunction "COM1_VBAT_P$101") (pintype "bidirectional"))
    )
    (net (code "80") (name "unconnected-(U$7-COM1_VBAT-PadP$103)") (class "Default")
      (node (ref "U$7") (pin "P$103") (pinfunction "COM1_VBAT_P$103") (pintype "bidirectional"))
    )
    (net (code "81") (name "unconnected-(U$7-COM2_GND-PadP$98)") (class "Default")
      (node (ref "U$7") (pin "P$98") (pinfunction "COM2_GND_P$98") (pintype "bidirectional"))
    )
    (net (code "82") (name "unconnected-(U$7-COM2_GND-PadP$100)") (class "Default")
      (node (ref "U$7") (pin "P$100") (pinfunction "COM2_GND_P$100") (pintype "bidirectional"))
    )
    (net (code "83") (name "unconnected-(U$7-COM2_VBAT-PadP$97)") (class "Default")
      (node (ref "U$7") (pin "P$97") (pinfunction "COM2_VBAT_P$97") (pintype "bidirectional"))
    )
    (net (code "84") (name "unconnected-(U$7-COM2_VBAT-PadP$99)") (class "Default")
      (node (ref "U$7") (pin "P$99") (pinfunction "COM2_VBAT_P$99") (pintype "bidirectional"))
    )
    (net (code "85") (name "unconnected-(U$7-ESTIMAT_GND-PadP$78)") (class "Default")
      (node (ref "U$7") (pin "P$78") (pinfunction "ESTIMAT_GND_P$78") (pintype "bidirectional"))
    )
    (net (code "86") (name "unconnected-(U$7-ESTIMAT_GND-PadP$80)") (class "Default")
      (node (ref "U$7") (pin "P$80") (pinfunction "ESTIMAT_GND_P$80") (pintype "bidirectional"))
    )
    (net (code "87") (name "unconnected-(U$7-ESTIMAT_I2C_SCL-PadP$70)") (class "Default")
      (node (ref "U$7") (pin "P$70") (pinfunction "ESTIMAT_I2C_SCL_P$70") (pintype "bidirectional"))
    )
    (net (code "88") (name "unconnected-(U$7-ESTIMAT_I2C_SDA-PadP$69)") (class "Default")
      (node (ref "U$7") (pin "P$69") (pinfunction "ESTIMAT_I2C_SDA_P$69") (pintype "bidirectional"))
    )
    (net (code "89") (name "unconnected-(U$7-ESTIMAT_VBAT-PadP$77)") (class "Default")
      (node (ref "U$7") (pin "P$77") (pinfunction "ESTIMAT_VBAT_P$77") (pintype "bidirectional"))
    )
    (net (code "90") (name "unconnected-(U$7-ESTIMAT_VBAT-PadP$79)") (class "Default")
      (node (ref "U$7") (pin "P$79") (pinfunction "ESTIMAT_VBAT_P$79") (pintype "bidirectional"))
    )
    (net (code "91") (name "unconnected-(U$7-MAG1_PWM-PadP$73)") (class "Default")
      (node (ref "U$7") (pin "P$73") (pinfunction "MAG1_PWM_P$73") (pintype "bidirectional"))
    )
    (net (code "92") (name "unconnected-(U$7-MAG2_PWM-PadP$74)") (class "Default")
      (node (ref "U$7") (pin "P$74") (pinfunction "MAG2_PWM_P$74") (pintype "bidirectional"))
    )
    (net (code "93") (name "unconnected-(U$7-MAG3_PWM-PadP$75)") (class "Default")
      (node (ref "U$7") (pin "P$75") (pinfunction "MAG3_PWM_P$75") (pintype "bidirectional"))
    )
    (net (code "94") (name "unconnected-(U$7-MCU_GND-PadP$46)") (class "Default")
      (node (ref "U$7") (pin "P$46") (pinfunction "MCU_GND_P$46") (pintype "bidirectional"))
    )
    (net (code "95") (name "unconnected-(U$7-MCU_GND-PadP$47)") (class "Default")
      (node (ref "U$7") (pin "P$47") (pinfunction "MCU_GND_P$47") (pintype "bidirectional"))
    )
    (net (code "96") (name "unconnected-(U$7-MCU_GND-PadP$58)") (class "Default")
      (node (ref "U$7") (pin "P$58") (pinfunction "MCU_GND_P$58") (pintype "bidirectional"))
    )
    (net (code "97") (name "unconnected-(U$7-MCU_GND-PadP$59)") (class "Default")
      (node (ref "U$7") (pin "P$59") (pinfunction "MCU_GND_P$59") (pintype "bidirectional"))
    )
    (net (code "98") (name "unconnected-(U$7-PPT_GND-PadP$1)") (class "Default")
      (node (ref "U$7") (pin "P$1") (pinfunction "PPT_GND_P$1") (pintype "bidirectional"))
    )
    (net (code "99") (name "unconnected-(U$7-PPT_GND-PadP$3)") (class "Default")
      (node (ref "U$7") (pin "P$3") (pinfunction "PPT_GND_P$3") (pintype "bidirectional"))
    )
    (net (code "100") (name "unconnected-(U$7-PPT_GND-PadP$6)") (class "Default")
      (node (ref "U$7") (pin "P$6") (pinfunction "PPT_GND_P$6") (pintype "bidirectional"))
    )
    (net (code "101") (name "unconnected-(U$7-PPT_GND-PadP$8)") (class "Default")
      (node (ref "U$7") (pin "P$8") (pinfunction "PPT_GND_P$8") (pintype "bidirectional"))
    )
    (net (code "102") (name "unconnected-(U$7-PPT_GND-PadP$9)") (class "Default")
      (node (ref "U$7") (pin "P$9") (pinfunction "PPT_GND_P$9") (pintype "bidirectional"))
    )
    (net (code "103") (name "unconnected-(U$7-PPT_GND-PadP$11)") (class "Default")
      (node (ref "U$7") (pin "P$11") (pinfunction "PPT_GND_P$11") (pintype "bidirectional"))
    )
    (net (code "104") (name "unconnected-(U$7-PPT_GND-PadP$14)") (class "Default")
      (node (ref "U$7") (pin "P$14") (pinfunction "PPT_GND_P$14") (pintype "bidirectional"))
    )
    (net (code "105") (name "unconnected-(U$7-PPT_GND-PadP$16)") (class "Default")
      (node (ref "U$7") (pin "P$16") (pinfunction "PPT_GND_P$16") (pintype "bidirectional"))
    )
    (net (code "106") (name "unconnected-(U$7-PPT_VBAT-PadP$2)") (class "Default")
      (node (ref "U$7") (pin "P$2") (pinfunction "PPT_VBAT_P$2") (pintype "bidirectional"))
    )
    (net (code "107") (name "unconnected-(U$7-PPT_VBAT-PadP$4)") (class "Default")
      (node (ref "U$7") (pin "P$4") (pinfunction "PPT_VBAT_P$4") (pintype "bidirectional"))
    )
    (net (code "108") (name "unconnected-(U$7-PPT_VBAT-PadP$5)") (class "Default")
      (node (ref "U$7") (pin "P$5") (pinfunction "PPT_VBAT_P$5") (pintype "bidirectional"))
    )
    (net (code "109") (name "unconnected-(U$7-PPT_VBAT-PadP$7)") (class "Default")
      (node (ref "U$7") (pin "P$7") (pinfunction "PPT_VBAT_P$7") (pintype "bidirectional"))
    )
    (net (code "110") (name "unconnected-(U$7-PPT_VBAT-PadP$10)") (class "Default")
      (node (ref "U$7") (pin "P$10") (pinfunction "PPT_VBAT_P$10") (pintype "bidirectional"))
    )
    (net (code "111") (name "unconnected-(U$7-PPT_VBAT-PadP$12)") (class "Default")
      (node (ref "U$7") (pin "P$12") (pinfunction "PPT_VBAT_P$12") (pintype "bidirectional"))
    )
    (net (code "112") (name "unconnected-(U$7-PPT_VBAT-PadP$13)") (class "Default")
      (node (ref "U$7") (pin "P$13") (pinfunction "PPT_VBAT_P$13") (pintype "bidirectional"))
    )
    (net (code "113") (name "unconnected-(U$7-PPT_VBAT-PadP$15)") (class "Default")
      (node (ref "U$7") (pin "P$15") (pinfunction "PPT_VBAT_P$15") (pintype "bidirectional"))
    )
    (net (code "114") (name "unconnected-(U$7-PadP$33)") (class "Default")
      (node (ref "U$7") (pin "P$33") (pinfunction "P$33_P$33") (pintype "bidirectional"))
    )
    (net (code "115") (name "unconnected-(U$7-PadP$34)") (class "Default")
      (node (ref "U$7") (pin "P$34") (pinfunction "P$34_P$34") (pintype "bidirectional"))
    )
    (net (code "116") (name "unconnected-(U$7-PadP$35)") (class "Default")
      (node (ref "U$7") (pin "P$35") (pinfunction "P$35_P$35") (pintype "bidirectional"))
    )
    (net (code "117") (name "unconnected-(U$7-PadP$36)") (class "Default")
      (node (ref "U$7") (pin "P$36") (pinfunction "P$36_P$36") (pintype "bidirectional"))
    )
    (net (code "118") (name "unconnected-(U$7-PadP$37)") (class "Default")
      (node (ref "U$7") (pin "P$37") (pinfunction "P$37_P$37") (pintype "bidirectional"))
    )
    (net (code "119") (name "unconnected-(U$7-PadP$38)") (class "Default")
      (node (ref "U$7") (pin "P$38") (pinfunction "P$38_P$38") (pintype "bidirectional"))
    )
    (net (code "120") (name "unconnected-(U$7-PadP$39)") (class "Default")
      (node (ref "U$7") (pin "P$39") (pinfunction "P$39_P$39") (pintype "bidirectional"))
    )
    (net (code "121") (name "unconnected-(U$7-PadP$40)") (class "Default")
      (node (ref "U$7") (pin "P$40") (pinfunction "P$40_P$40") (pintype "bidirectional"))
    )
    (net (code "122") (name "unconnected-(U$7-PadP$41)") (class "Default")
      (node (ref "U$7") (pin "P$41") (pinfunction "P$41_P$41") (pintype "bidirectional"))
    )
    (net (code "123") (name "unconnected-(U$7-PadP$42)") (class "Default")
      (node (ref "U$7") (pin "P$42") (pinfunction "P$42_P$42") (pintype "bidirectional"))
    )
    (net (code "124") (name "unconnected-(U$7-PadP$43)") (class "Default")
      (node (ref "U$7") (pin "P$43") (pinfunction "P$43_P$43") (pintype "bidirectional"))
    )
    (net (code "125") (name "unconnected-(U$7-PadP$44)") (class "Default")
      (node (ref "U$7") (pin "P$44") (pinfunction "P$44_P$44") (pintype "bidirectional"))
    )
    (net (code "126") (name "unconnected-(U$7-PadP$48)") (class "Default")
      (node (ref "U$7") (pin "P$48") (pinfunction "P$48_P$48") (pintype "bidirectional"))
    )
    (net (code "127") (name "unconnected-(U$7-PadP$52)") (class "Default")
      (node (ref "U$7") (pin "P$52") (pinfunction "P$52_P$52") (pintype "bidirectional"))
    )
    (net (code "128") (name "unconnected-(U$7-PadP$56)") (class "Default")
      (node (ref "U$7") (pin "P$56") (pinfunction "P$56_P$56") (pintype "bidirectional"))
    )
    (net (code "129") (name "unconnected-(U$7-PadP$60)") (class "Default")
      (node (ref "U$7") (pin "P$60") (pinfunction "P$60_P$60") (pintype "bidirectional"))
    )
    (net (code "130") (name "unconnected-(U$7-PadP$61)") (class "Default")
      (node (ref "U$7") (pin "P$61") (pinfunction "P$61_P$61") (pintype "bidirectional"))
    )
    (net (code "131") (name "unconnected-(U$7-PadP$62)") (class "Default")
      (node (ref "U$7") (pin "P$62") (pinfunction "P$62_P$62") (pintype "bidirectional"))
    )
    (net (code "132") (name "unconnected-(U$7-PadP$63)") (class "Default")
      (node (ref "U$7") (pin "P$63") (pinfunction "P$63_P$63") (pintype "bidirectional"))
    )
    (net (code "133") (name "unconnected-(U$7-PadP$64)") (class "Default")
      (node (ref "U$7") (pin "P$64") (pinfunction "P$64_P$64") (pintype "bidirectional"))
    )
    (net (code "134") (name "unconnected-(U$7-PadP$65)") (class "Default")
      (node (ref "U$7") (pin "P$65") (pinfunction "P$65_P$65") (pintype "bidirectional"))
    )
    (net (code "135") (name "unconnected-(U$7-PadP$66)") (class "Default")
      (node (ref "U$7") (pin "P$66") (pinfunction "P$66_P$66") (pintype "bidirectional"))
    )
    (net (code "136") (name "unconnected-(U$7-PadP$67)") (class "Default")
      (node (ref "U$7") (pin "P$67") (pinfunction "P$67_P$67") (pintype "bidirectional"))
    )
    (net (code "137") (name "unconnected-(U$7-PadP$68)") (class "Default")
      (node (ref "U$7") (pin "P$68") (pinfunction "P$68_P$68") (pintype "bidirectional"))
    )
    (net (code "138") (name "unconnected-(U$7-PadP$71)") (class "Default")
      (node (ref "U$7") (pin "P$71") (pinfunction "P$71_P$71") (pintype "bidirectional"))
    )
    (net (code "139") (name "unconnected-(U$7-PadP$72)") (class "Default")
      (node (ref "U$7") (pin "P$72") (pinfunction "P$72_P$72") (pintype "bidirectional"))
    )
    (net (code "140") (name "unconnected-(U$7-PadP$76)") (class "Default")
      (node (ref "U$7") (pin "P$76") (pinfunction "P$76_P$76") (pintype "bidirectional"))
    )
    (net (code "141") (name "unconnected-(U$7-PadP$91)") (class "Default")
      (node (ref "U$7") (pin "P$91") (pinfunction "P$91_P$91") (pintype "bidirectional"))
    )
    (net (code "142") (name "unconnected-(U$7-PadP$92)") (class "Default")
      (node (ref "U$7") (pin "P$92") (pinfunction "P$92_P$92") (pintype "bidirectional"))
    )
    (net (code "143") (name "unconnected-(U$7-PadP$95)") (class "Default")
      (node (ref "U$7") (pin "P$95") (pinfunction "P$95_P$95") (pintype "bidirectional"))
    )
    (net (code "144") (name "unconnected-(U$7-PadP$96)") (class "Default")
      (node (ref "U$7") (pin "P$96") (pinfunction "P$96_P$96") (pintype "bidirectional"))
    )
    (net (code "145") (name "unconnected-(U$7-RAHS_GND-PadP$94)") (class "Default")
      (node (ref "U$7") (pin "P$94") (pinfunction "RAHS_GND_P$94") (pintype "bidirectional"))
    )
    (net (code "146") (name "unconnected-(U$7-RAHS_VBAT-PadP$93)") (class "Default")
      (node (ref "U$7") (pin "P$93") (pinfunction "RAHS_VBAT_P$93") (pintype "bidirectional"))
    )
  )
)
